# qtip_s1.net
KiCad netlist of a schematic drawn in EAGLE
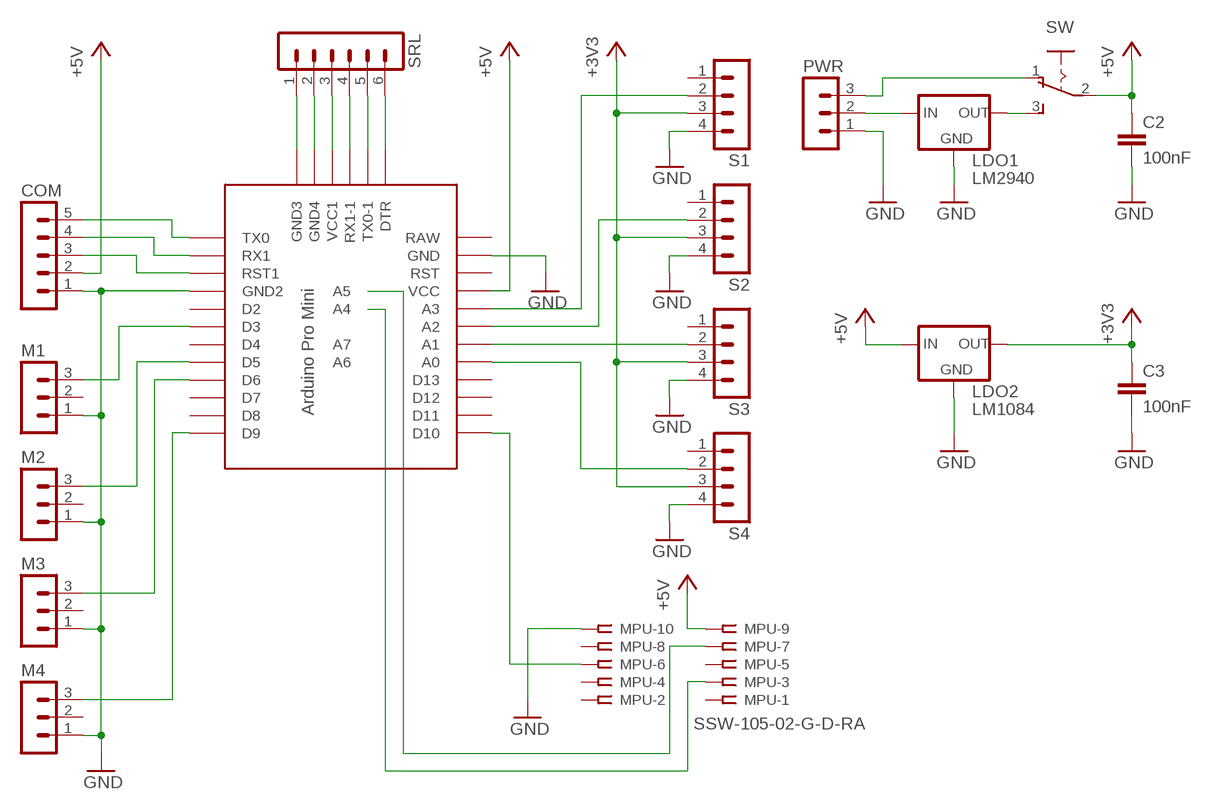
[diagram p0: schematic, sheet 1]

(export (version "E")
  (design (tool "Eeschema 10.0.6"))
  (components
    (comp (ref "C2")
      (value "100nF")
      (footprint "eagle-import:C025-024X044")
      (libsource (lib "eagle-import") (part "C-EU025-024X044"))
    )
    (comp (ref "C3")
      (value "100nF")
      (footprint "eagle-import:C025-024X044")
      (libsource (lib "eagle-import") (part "C-EU025-024X044"))
    )
    (comp (ref "COM")
      (value "MA05-1")
      (footprint "eagle-import:MA05-1")
      (fields (field (name "SPICEPREFIX") "X"))
      (libsource (lib "eagle-import") (part "MA05-1"))
    )
    (comp (ref "LDO1")
      (value "LM2940")
      (footprint "eagle-import:78XXL")
      (libsource (lib "eagle-import") (part "V_REG_LD1117VXX"))
    )
    (comp (ref "LDO2")
      (value "LM1084")
      (footprint "eagle-import:78XXL")
      (libsource (lib "eagle-import") (part "V_REG_LD1117VXX"))
    )
    (comp (ref "M1")
      (value "MA03-1")
      (footprint "eagle-import:MA03-1")
      (libsource (lib "eagle-import") (part "MA03-1"))
    )
    (comp (ref "M2")
      (value "MA03-1")
      (footprint "eagle-import:MA03-1")
      (libsource (lib "eagle-import") (part "MA03-1"))
    )
    (comp (ref "M3")
      (value "MA03-1")
      (footprint "eagle-import:MA03-1")
      (libsource (lib "eagle-import") (part "MA03-1"))
    )
    (comp (ref "M4")
      (value "MA03-1")
      (footprint "eagle-import:MA03-1")
      (libsource (lib "eagle-import") (part "MA03-1"))
    )
    (comp (ref "MPU")
      (value "SSW-105-02-G-D-RA")
      (footprint "eagle-import:SSW-105-02-G-D-RA")
      (fields (field (name "MF") "Samtec Inc."))
      (libsource (lib "eagle-import") (part "SSW-105-02-G-D-RA"))
    )
    (comp (ref "PWR")
      (value "MA03-1")
      (footprint "eagle-import:MA03-1")
      (libsource (lib "eagle-import") (part "MA03-1"))
    )
    (comp (ref "S1")
      (value "MA04-1")
      (footprint "eagle-import:MA04-1")
      (libsource (lib "eagle-import") (part "MA04-1"))
    )
    (comp (ref "S2")
      (value "MA04-1")
      (footprint "eagle-import:MA04-1")
      (libsource (lib "eagle-import") (part "MA04-1"))
    )
    (comp (ref "S3")
      (value "MA04-1")
      (footprint "eagle-import:MA04-1")
      (libsource (lib "eagle-import") (part "MA04-1"))
    )
    (comp (ref "S4")
      (value "MA04-1")
      (footprint "eagle-import:MA04-1")
      (libsource (lib "eagle-import") (part "MA04-1"))
    )
    (comp (ref "SRL")
      (value "MA06-1")
      (footprint "eagle-import:MA06-1")
      (libsource (lib "eagle-import") (part "MA06-1"))
    )
    (comp (ref "SW")
      (value "255SB")
      (footprint "eagle-import:255SB")
      (libsource (lib "eagle-import") (part "255SB"))
    )
    (comp (ref "ÀPM")
      (value "PRO-MINI-2")
      (footprint "eagle-import:PRO-MINI-2")
      (libsource (lib "eagle-import") (part "PRO-MINI-2"))
    )
  )
  (nets
    (net (code "1") (name "+3V3") (class "Default")
      (node (ref "C3") (pin "1") (pinfunction "1_1") (pintype "passive"))
      (node (ref "LDO2") (pin "GND") (pinfunction "OUT_GND") (pintype "passive"))
      (node (ref "S1") (pin "3") (pinfunction "3_3") (pintype "passive"))
      (node (ref "S2") (pin "3") (pinfunction "3_3") (pintype "passive"))
      (node (ref "S3") (pin "3") (pinfunction "3_3") (pintype "passive"))
      (node (ref "S4") (pin "3") (pinfunction "3_3") (pintype "passive"))
    )
    (net (code "2") (name "+5V") (class "Default")
      (node (ref "C2") (pin "1") (pinfunction "1_1") (pintype "passive"))
      (node (ref "COM") (pin "2") (pinfunction "2_2") (pintype "passive"))
      (node (ref "LDO2") (pin "OUT") (pinfunction "IN_OUT") (pintype "input"))
      (node (ref "MPU") (pin "9") (pinfunction "1_9") (pintype "passive"))
      (node (ref "SW") (pin "2") (pinfunction "P_2") (pintype "passive"))
      (node (ref "ÀPM") (pin "VCC") (pinfunction "VCC_VCC") (pintype "bidirectional"))
    )
    (net (code "3") (name "GND") (class "Default")
      (node (ref "C2") (pin "2") (pinfunction "2_2") (pintype "passive"))
      (node (ref "C3") (pin "2") (pinfunction "2_2") (pintype "passive"))
      (node (ref "COM") (pin "1") (pinfunction "1_1") (pintype "passive"))
      (node (ref "LDO1") (pin "IN") (pinfunction "GND_IN") (pintype "input"))
      (node (ref "LDO2") (pin "IN") (pinfunction "GND_IN") (pintype "input"))
      (node (ref "M1") (pin "1") (pinfunction "1_1") (pintype "passive"))
      (node (ref "M2") (pin "1") (pinfunction "1_1") (pintype "passive"))
      (node (ref "M3") (pin "1") (pinfunction "1_1") (pintype "passive"))
      (node (ref "M4") (pin "1") (pinfunction "1_1") (pintype "passive"))
      (node (ref "MPU") (pin "10") (pinfunction "1_10") (pintype "passive"))
      (node (ref "PWR") (pin "1") (pinfunction "1_1") (pintype "passive"))
      (node (ref "S1") (pin "4") (pinfunction "4_4") (pintype "passive"))
      (node (ref "S2") (pin "4") (pinfunction "4_4") (pintype "passive"))
      (node (ref "S3") (pin "4") (pinfunction "4_4") (pintype "passive"))
      (node (ref "S4") (pin "4") (pinfunction "4_4") (pintype "passive"))
      (node (ref "ÀPM") (pin "GND") (pinfunction "GND_GND") (pintype "bidirectional"))
      (node (ref "ÀPM") (pin "GND1") (pinfunction "GND2_GND1") (pintype "bidirectional"))
    )
    (net (code "4") (name "Net-(COM-Pad3)") (class "Default")
      (node (ref "COM") (pin "3") (pinfunction "3_3") (pintype "passive"))
      (node (ref "ÀPM") (pin "RST1") (pinfunction "RST1_RST1") (pintype "bidirectional"))
    )
    (net (code "5") (name "Net-(COM-Pad4)") (class "Default")
      (node (ref "COM") (pin "4") (pinfunction "4_4") (pintype "passive"))
      (node (ref "ÀPM") (pin "RX1") (pinfunction "RX1_RX1") (pintype "bidirectional"))
    )
    (net (code "6") (name "Net-(COM-Pad5)") (class "Default")
      (node (ref "COM") (pin "5") (pinfunction "5_5") (pintype "passive"))
      (node (ref "ÀPM") (pin "TX0") (pinfunction "TX0_TX0") (pintype "bidirectional"))
    )
    (net (code "7") (name "Net-(LDO1-IN)") (class "Default")
      (node (ref "LDO1") (pin "OUT") (pinfunction "IN_OUT") (pintype "input"))
      (node (ref "PWR") (pin "2") (pinfunction "2_2") (pintype "passive"))
    )
    (net (code "8") (name "Net-(LDO1-OUT)") (class "Default")
      (node (ref "LDO1") (pin "GND") (pinfunction "OUT_GND") (pintype "passive"))
      (node (ref "SW") (pin "3") (pinfunction "S_3") (pintype "passive"))
    )
    (net (code "9") (name "Net-(M1-Pad3)") (class "Default")
      (node (ref "M1") (pin "3") (pinfunction "3_3") (pintype "passive"))
      (node (ref "ÀPM") (pin "D3") (pinfunction "D3_D3") (pintype "bidirectional"))
    )
    (net (code "10") (name "Net-(M2-Pad3)") (class "Default")
      (node (ref "M2") (pin "3") (pinfunction "3_3") (pintype "passive"))
      (node (ref "ÀPM") (pin "D5") (pinfunction "D5_D5") (pintype "bidirectional"))
    )
    (net (code "11") (name "Net-(M3-Pad3)") (class "Default")
      (node (ref "M3") (pin "3") (pinfunction "3_3") (pintype "passive"))
      (node (ref "ÀPM") (pin "D6") (pinfunction "D6_D6") (pintype "bidirectional"))
    )
    (net (code "12") (name "Net-(M4-Pad3)") (class "Default")
      (node (ref "M4") (pin "3") (pinfunction "3_3") (pintype "passive"))
      (node (ref "ÀPM") (pin "D9") (pinfunction "D9_D9") (pintype "bidirectional"))
    )
    (net (code "13") (name "Net-(MPUD-1)") (class "Default")
      (node (ref "MPU") (pin "3") (pinfunction "1_3") (pintype "passive"))
      (node (ref "ÀPM") (pin "A4") (pinfunction "A4_A4") (pintype "bidirectional"))
    )
    (net (code "14") (name "Net-(MPUG-1)") (class "Default")
      (node (ref "MPU") (pin "6") (pinfunction "1_6") (pintype "passive"))
      (node (ref "ÀPM") (pin "D10") (pinfunction "D10_D10") (pintype "bidirectional"))
    )
    (net (code "15") (name "Net-(MPUH-1)") (class "Default")
      (node (ref "MPU") (pin "7") (pinfunction "1_7") (pintype "passive"))
      (node (ref "ÀPM") (pin "A5") (pinfunction "A5_A5") (pintype "bidirectional"))
    )
    (net (code "16") (name "Net-(S1-Pad2)") (class "Default")
      (node (ref "S1") (pin "2") (pinfunction "2_2") (pintype "passive"))
      (node (ref "ÀPM") (pin "A3") (pinfunction "A3_A3") (pintype "bidirectional"))
    )
    (net (code "17") (name "Net-(S2-Pad2)") (class "Default")
      (node (ref "S2") (pin "2") (pinfunction "2_2") (pintype "passive"))
      (node (ref "ÀPM") (pin "A2") (pinfunction "A2_A2") (pintype "bidirectional"))
    )
    (net (code "18") (name "Net-(S3-Pad2)") (class "Default")
      (node (ref "S3") (pin "2") (pinfunction "2_2") (pintype "passive"))
      (node (ref "ÀPM") (pin "A1") (pinfunction "A1_A1") (pintype "bidirectional"))
    )
    (net (code "19") (name "Net-(S4-Pad2)") (class "Default")
      (node (ref "S4") (pin "2") (pinfunction "2_2") (pintype "passive"))
      (node (ref "ÀPM") (pin "A0") (pinfunction "A0_A0") (pintype "bidirectional"))
    )
    (net (code "20") (name "Net-(SRL-Pad3)") (class "Default")
      (node (ref "SRL") (pin "3") (pinfunction "3_3") (pintype "passive"))
      (node (ref "ÀPM") (pin "VCC1") (pinfunction "VCC1_VCC1") (pintype "bidirectional"))
    )
    (net (code "21") (name "Net-(SRL-Pad4)") (class "Default")
      (node (ref "SRL") (pin "4") (pinfunction "4_4") (pintype "passive"))
      (node (ref "ÀPM") (pin "RX1-1") (pinfunction "RX1-1_RX1-1") (pintype "bidirectional"))
    )
    (net (code "22") (name "Net-(SRL-Pad5)") (class "Default")
      (node (ref "SRL") (pin "5") (pinfunction "5_5") (pintype "passive"))
      (node (ref "ÀPM") (pin "TX0-1") (pinfunction "TX0-1_TX0-1") (pintype "bidirectional"))
    )
    (net (code "23") (name "Net-(SRL-Pad6)") (class "Default")
      (node (ref "SRL") (pin "6") (pinfunction "6_6") (pintype "passive"))
      (node (ref "ÀPM") (pin "DTR") (pinfunction "DTR_DTR") (pintype "bidirectional"))
    )
    (net (code "24") (name "Net-(SW-O)") (class "Default")
      (node (ref "PWR") (pin "3") (pinfunction "3_3") (pintype "passive"))
      (node (ref "SW") (pin "1") (pinfunction "O_1") (pintype "passive"))
    )
    (net (code "25") (name "Net-(ÀPM-GND3)") (class "Default")
      (node (ref "SRL") (pin "1") (pinfunction "1_1") (pintype "passive"))
      (node (ref "ÀPM") (pin "GND2") (pinfunction "GND3_GND2") (pintype "bidirectional"))
    )
    (net (code "26") (name "Net-(ÀPM-GND4)") (class "Default")
      (node (ref "SRL") (pin "2") (pinfunction "2_2") (pintype "passive"))
      (node (ref "ÀPM") (pin "GND3") (pinfunction "GND4_GND3") (pintype "bidirectional"))
    )
    (net (code "27") (name "unconnected-(M1-Pad2)") (class "Default")
      (node (ref "M1") (pin "2") (pinfunction "2_2") (pintype "passive"))
    )
    (net (code "28") (name "unconnected-(M2-Pad2)") (class "Default")
      (node (ref "M2") (pin "2") (pinfunction "2_2") (pintype "passive"))
    )
    (net (code "29") (name "unconnected-(M3-Pad2)") (class "Default")
      (node (ref "M3") (pin "2") (pinfunction "2_2") (pintype "passive"))
    )
    (net (code "30") (name "unconnected-(M4-Pad2)") (class "Default")
      (node (ref "M4") (pin "2") (pinfunction "2_2") (pintype "passive"))
    )
    (net (code "31") (name "unconnected-(MPU-Pad1)") (class "Default")
      (node (ref "MPU") (pin "1") (pinfunction "1_1") (pintype "passive"))
    )
    (net (code "32") (name "unconnected-(MPUC-1-Pad2)") (class "Default")
      (node (ref "MPU") (pin "2") (pinfunction "1_2") (pintype "passive"))
    )
    (net (code "33") (name "unconnected-(MPUE-1-Pad4)") (class "Default")
      (node (ref "MPU") (pin "4") (pinfunction "1_4") (pintype "passive"))
    )
    (net (code "34") (name "unconnected-(MPUF-1-Pad5)") (class "Default")
      (node (ref "MPU") (pin "5") (pinfunction "1_5") (pintype "passive"))
    )
    (net (code "35") (name "unconnected-(MPUI-1-Pad8)") (class "Default")
      (node (ref "MPU") (pin "8") (pinfunction "1_8") (pintype "passive"))
    )
    (net (code "36") (name "unconnected-(S1-Pad1)") (class "Default")
      (node (ref "S1") (pin "1") (pinfunction "1_1") (pintype "passive"))
    )
    (net (code "37") (name "unconnected-(S2-Pad1)") (class "Default")
      (node (ref "S2") (pin "1") (pinfunction "1_1") (pintype "passive"))
    )
    (net (code "38") (name "unconnected-(S3-Pad1)") (class "Default")
      (node (ref "S3") (pin "1") (pinfunction "1_1") (pintype "passive"))
    )
    (net (code "39") (name "unconnected-(S4-Pad1)") (class "Default")
      (node (ref "S4") (pin "1") (pinfunction "1_1") (pintype "passive"))
    )
    (net (code "40") (name "unconnected-(ÀPM-PadA6)") (class "Default")
      (node (ref "ÀPM") (pin "A6") (pinfunction "A6_A6") (pintype "bidirectional"))
    )
    (net (code "41") (name "unconnected-(ÀPM-PadA7)") (class "Default")
      (node (ref "ÀPM") (pin "A7") (pinfunction "A7_A7") (pintype "bidirectional"))
    )
    (net (code "42") (name "unconnected-(ÀPM-PadD2)") (class "Default")
      (node (ref "ÀPM") (pin "D2") (pinfunction "D2_D2") (pintype "bidirectional"))
    )
    (net (code "43") (name "unconnected-(ÀPM-PadD4)") (class "Default")
      (node (ref "ÀPM") (pin "D4") (pinfunction "D4_D4") (pintype "bidirectional"))
    )
    (net (code "44") (name "unconnected-(ÀPM-PadD7)") (class "Default")
      (node (ref "ÀPM") (pin "D7") (pinfunction "D7_D7") (pintype "bidirectional"))
    )
    (net (code "45") (name "unconnected-(ÀPM-PadD8)") (class "Default")
      (node (ref "ÀPM") (pin "D8") (pinfunction "D8_D8") (pintype "bidirectional"))
    )
    (net (code "46") (name "unconnected-(ÀPM-PadD11)") (class "Default")
      (node (ref "ÀPM") (pin "D11") (pinfunction "D11_D11") (pintype "bidirectional"))
    )
    (net (code "47") (name "unconnected-(ÀPM-PadD12)") (class "Default")
      (node (ref "ÀPM") (pin "D12") (pinfunction "D12_D12") (pintype "bidirectional"))
    )
    (net (code "48") (name "unconnected-(ÀPM-PadD13)") (class "Default")
      (node (ref "ÀPM") (pin "D13") (pinfunction "D13_D13") (pintype "bidirectional"))
    )
    (net (code "49") (name "unconnected-(ÀPM-PadRAW)") (class "Default")
      (node (ref "ÀPM") (pin "RAW") (pinfunction "RAW_RAW") (pintype "bidirectional"))
    )
    (net (code "50") (name "unconnected-(ÀPM-PadRST)") (class "Default")
      (node (ref "ÀPM") (pin "RST") (pinfunction "RST_RST") (pintype "bidirectional"))
    )
  )
)
